# schematic.net
KiCad netlist of a schematic drawn in Altium Designer
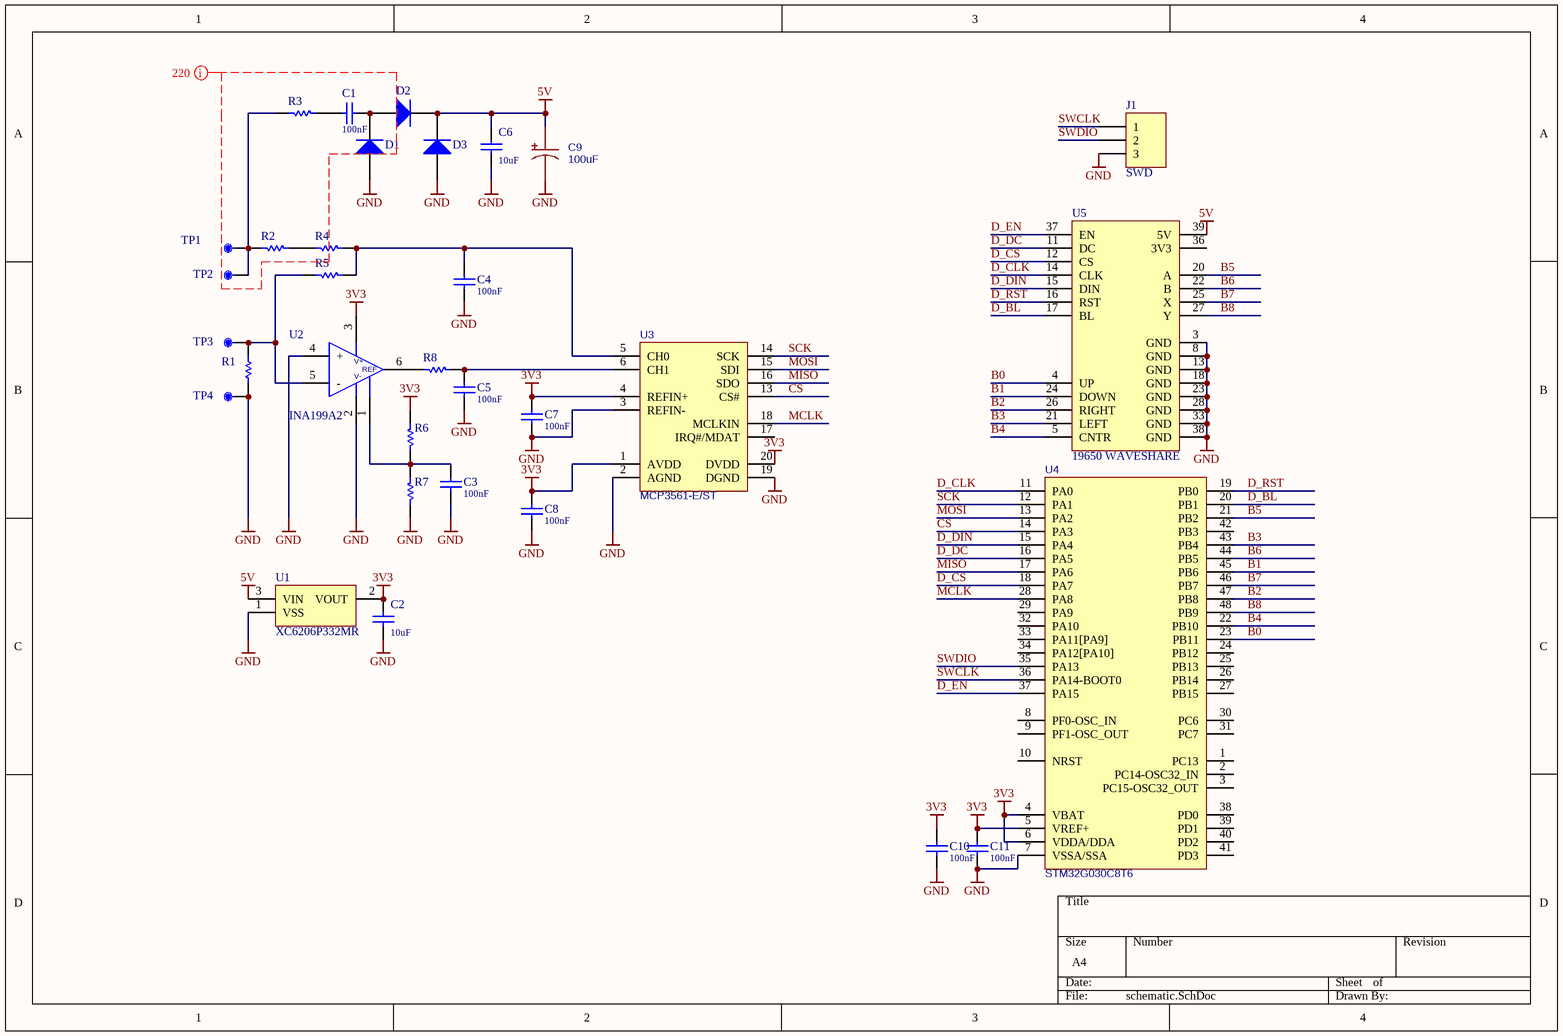
[diagram p0: schematic.SchDoc]

(export (version "E")
  (design (tool "Eeschema 10.0.6"))
  (components
    (comp (ref "C1")
      (value "100nF")
      (footprint "CAP-TH_27,5")
      (libsource (lib "Miscellaneous Devices") (part "CAP"))
    )
    (comp (ref "C2")
      (value "10uF")
      (footprint "C1206")
      (libsource (lib "Miscellaneous Devices") (part "CAP"))
    )
    (comp (ref "C3")
      (value "100nF")
      (footprint "C0402")
      (libsource (lib "Miscellaneous Devices") (part "CAP"))
    )
    (comp (ref "C4")
      (value "100nF")
      (footprint "C0402")
      (libsource (lib "Miscellaneous Devices") (part "CAP"))
    )
    (comp (ref "C5")
      (value "100nF")
      (footprint "C0402")
      (libsource (lib "Miscellaneous Devices") (part "CAP"))
    )
    (comp (ref "C6")
      (value "10uF")
      (footprint "C1206")
      (libsource (lib "Miscellaneous Devices") (part "CAP"))
    )
    (comp (ref "C7")
      (value "100nF")
      (footprint "C0402")
      (libsource (lib "Miscellaneous Devices") (part "CAP"))
    )
    (comp (ref "C8")
      (value "100nF")
      (footprint "C0402")
      (libsource (lib "Miscellaneous Devices") (part "CAP"))
    )
    (comp (ref "C9")
      (value "100uF")
      (footprint "C7343")
      (libsource (lib "altium-import") (part "root_0_220uF_"))
    )
    (comp (ref "C10")
      (value "100nF")
      (footprint "C0402")
      (libsource (lib "Miscellaneous Devices") (part "CAP"))
    )
    (comp (ref "C11")
      (value "100nF")
      (footprint "C0402")
      (libsource (lib "Miscellaneous Devices") (part "CAP"))
    )
    (comp (ref "D1")
      (value "~")
      (footprint "DO-41")
      (libsource (lib "Miscellaneous Devices") (part "US1M-13-F"))
    )
    (comp (ref "D2")
      (value "~")
      (footprint "DO-41")
      (libsource (lib "Miscellaneous Devices") (part "US1M-13-F"))
    )
    (comp (ref "D3")
      (value "~")
      (footprint "SMA")
      (libsource (lib "Miscellaneous Devices") (part "US1M-13-F"))
    )
    (comp (ref "J1")
      (value "SWD")
      (footprint "HDR-1X3")
      (libsource (lib "Miscellaneous Devices") (part "Header 3"))
    )
    (comp (ref "R1")
      (value "~")
      (footprint "R2512-WIDE")
      (libsource (lib "Miscellaneous Devices") (part "RES"))
    )
    (comp (ref "R2") (value "~") (footprint "R1206") (libsource (lib "Miscellaneous Devices") (part "RES")))
    (comp (ref "R3")
      (value "~")
      (footprint "RES-TH_20")
      (libsource (lib "Miscellaneous Devices") (part "RES"))
    )
    (comp (ref "R4") (value "~") (footprint "R1206") (libsource (lib "Miscellaneous Devices") (part "RES")))
    (comp (ref "R5") (value "~") (footprint "R1206") (libsource (lib "Miscellaneous Devices") (part "RES")))
    (comp (ref "R6") (value "~") (footprint "R0603") (libsource (lib "Miscellaneous Devices") (part "RES")))
    (comp (ref "R7") (value "~") (footprint "R0603") (libsource (lib "Miscellaneous Devices") (part "RES")))
    (comp (ref "R8") (value "~") (footprint "R0603") (libsource (lib "Miscellaneous Devices") (part "RES")))
    (comp (ref "TP1")
      (value "~")
      (footprint "TP2030_SMD")
      (libsource (lib "Miscellaneous Devices") (part "TP_Dup1"))
    )
    (comp (ref "TP2")
      (value "~")
      (footprint "TP2030_SMD")
      (libsource (lib "Miscellaneous Devices") (part "TP_Dup1"))
    )
    (comp (ref "TP3")
      (value "~")
      (footprint "TP2030_SMD")
      (libsource (lib "Miscellaneous Devices") (part "TP_Dup1"))
    )
    (comp (ref "TP4")
      (value "~")
      (footprint "TP2030_SMD")
      (libsource (lib "Miscellaneous Devices") (part "TP_Dup1"))
    )
    (comp (ref "U1")
      (value "XC6206P332MR")
      (footprint "SOT-23")
      (libsource (lib "Schlib1") (part "Component_4_1"))
    )
    (comp (ref "U2")
      (value "INA199A2")
      (footprint "SOT-363")
      (libsource (lib "Miscellaneous Devices") (part "MCP65R41T-2402"))
    )
    (comp (ref "U3")
      (value "MCP3561-E/ST")
      (footprint "SSOP-20")
      (libsource (lib "Schlib1") (part "MCP3561-E/ST"))
    )
    (comp (ref "U4")
      (value "STM32G030C8T6")
      (footprint "LQFP-48")
      (libsource (lib "Schlib1") (part "STM32G030C8T6"))
    )
    (comp (ref "U5")
      (value "19650 WAVESHARE")
      (footprint "DISP_19650_WS")
      (libsource (lib "Schlib1") (part "19650 WAVESHARE"))
    )
  )
  (nets
    (net (code "1") (name "/B0") (class "Default")
      (node (ref "U4") (pin "23") (pinfunction "PB11_23") (pintype "passive"))
      (node (ref "U5") (pin "4") (pinfunction "UP_4") (pintype "passive"))
    )
    (net (code "2") (name "/B1") (class "Default")
      (node (ref "U4") (pin "45") (pinfunction "PB6_45") (pintype "passive"))
      (node (ref "U5") (pin "24") (pinfunction "DOWN_24") (pintype "passive"))
    )
    (net (code "3") (name "/B2") (class "Default")
      (node (ref "U4") (pin "47") (pinfunction "PB8_47") (pintype "passive"))
      (node (ref "U5") (pin "26") (pinfunction "RIGHT_26") (pintype "passive"))
    )
    (net (code "4") (name "/B3") (class "Default")
      (node (ref "U4") (pin "43") (pinfunction "PB4_43") (pintype "passive"))
      (node (ref "U5") (pin "21") (pinfunction "LEFT_21") (pintype "passive"))
    )
    (net (code "5") (name "/B4") (class "Default")
      (node (ref "U4") (pin "22") (pinfunction "PB10_22") (pintype "passive"))
      (node (ref "U5") (pin "5") (pinfunction "CNTR_5") (pintype "passive"))
    )
    (net (code "6") (name "/B5") (class "Default")
      (node (ref "U4") (pin "21") (pinfunction "PB2_21") (pintype "passive"))
      (node (ref "U5") (pin "20") (pinfunction "A_20") (pintype "passive"))
    )
    (net (code "7") (name "/B6") (class "Default")
      (node (ref "U4") (pin "44") (pinfunction "PB5_44") (pintype "passive"))
      (node (ref "U5") (pin "22") (pinfunction "B_22") (pintype "passive"))
    )
    (net (code "8") (name "/B7") (class "Default")
      (node (ref "U4") (pin "46") (pinfunction "PB7_46") (pintype "passive"))
      (node (ref "U5") (pin "25") (pinfunction "X_25") (pintype "passive"))
    )
    (net (code "9") (name "/B8") (class "Default")
      (node (ref "U4") (pin "48") (pinfunction "PB9_48") (pintype "passive"))
      (node (ref "U5") (pin "27") (pinfunction "Y_27") (pintype "passive"))
    )
    (net (code "10") (name "/CS") (class "Default")
      (node (ref "U3") (pin "13") (pinfunction "CS#_13") (pintype "passive"))
      (node (ref "U4") (pin "14") (pinfunction "PA3_14") (pintype "passive"))
    )
    (net (code "11") (name "/D_BL") (class "Default")
      (node (ref "U4") (pin "20") (pinfunction "PB1_20") (pintype "passive"))
      (node (ref "U5") (pin "17") (pinfunction "BL_17") (pintype "passive"))
    )
    (net (code "12") (name "/D_CLK") (class "Default")
      (node (ref "U4") (pin "11") (pinfunction "PA0_11") (pintype "passive"))
      (node (ref "U5") (pin "14") (pinfunction "CLK_14") (pintype "passive"))
    )
    (net (code "13") (name "/D_CS") (class "Default")
      (node (ref "U4") (pin "18") (pinfunction "PA7_18") (pintype "passive"))
      (node (ref "U5") (pin "12") (pinfunction "CS_12") (pintype "passive"))
    )
    (net (code "14") (name "/D_DC") (class "Default")
      (node (ref "U4") (pin "16") (pinfunction "PA5_16") (pintype "passive"))
      (node (ref "U5") (pin "11") (pinfunction "DC_11") (pintype "passive"))
    )
    (net (code "15") (name "/D_DIN") (class "Default")
      (node (ref "U4") (pin "15") (pinfunction "PA4_15") (pintype "passive"))
      (node (ref "U5") (pin "15") (pinfunction "DIN_15") (pintype "passive"))
    )
    (net (code "16") (name "/D_EN") (class "Default")
      (node (ref "U4") (pin "37") (pinfunction "PA15_37") (pintype "passive"))
      (node (ref "U5") (pin "37") (pinfunction "EN_37") (pintype "passive"))
    )
    (net (code "17") (name "/D_RST") (class "Default")
      (node (ref "U4") (pin "19") (pinfunction "PB0_19") (pintype "passive"))
      (node (ref "U5") (pin "16") (pinfunction "RST_16") (pintype "passive"))
    )
    (net (code "18") (name "/MCLK") (class "Default")
      (node (ref "U3") (pin "18") (pinfunction "MCLKIN_18") (pintype "passive"))
      (node (ref "U4") (pin "28") (pinfunction "PA8_28") (pintype "passive"))
    )
    (net (code "19") (name "/MISO") (class "Default")
      (node (ref "U3") (pin "16") (pinfunction "SDO_16") (pintype "passive"))
      (node (ref "U4") (pin "17") (pinfunction "PA6_17") (pintype "passive"))
    )
    (net (code "20") (name "/MOSI") (class "Default")
      (node (ref "U3") (pin "15") (pinfunction "SDI_15") (pintype "passive"))
      (node (ref "U4") (pin "13") (pinfunction "PA2_13") (pintype "passive"))
    )
    (net (code "21") (name "/SCK") (class "Default")
      (node (ref "U3") (pin "14") (pinfunction "SCK_14") (pintype "passive"))
      (node (ref "U4") (pin "12") (pinfunction "PA1_12") (pintype "passive"))
    )
    (net (code "22") (name "/SWCLK") (class "Default")
      (node (ref "J1") (pin "1") (pinfunction "1_1") (pintype "passive"))
      (node (ref "U4") (pin "36") (pinfunction "PA14-BOOT0_36") (pintype "passive"))
    )
    (net (code "23") (name "/SWDIO") (class "Default")
      (node (ref "J1") (pin "2") (pinfunction "2_2") (pintype "passive"))
      (node (ref "U4") (pin "35") (pinfunction "PA13_35") (pintype "passive"))
    )
    (net (code "24") (name "3V3") (class "Default")
      (node (ref "C10") (pin "2") (pinfunction "2_2") (pintype "passive"))
      (node (ref "C11") (pin "2") (pinfunction "2_2") (pintype "passive"))
      (node (ref "C2") (pin "2") (pinfunction "2_2") (pintype "passive"))
      (node (ref "C7") (pin "2") (pinfunction "2_2") (pintype "passive"))
      (node (ref "C8") (pin "2") (pinfunction "2_2") (pintype "passive"))
      (node (ref "R6") (pin "2") (pinfunction "2_2") (pintype "passive"))
      (node (ref "U1") (pin "2") (pinfunction "VOUT_2") (pintype "passive"))
      (node (ref "U2") (pin "3") (pinfunction "V+_3") (pintype "passive"))
      (node (ref "U3") (pin "1") (pinfunction "AVDD_1") (pintype "passive"))
      (node (ref "U3") (pin "20") (pinfunction "DVDD_20") (pintype "passive"))
      (node (ref "U3") (pin "4") (pinfunction "REFIN+_4") (pintype "passive"))
      (node (ref "U4") (pin "4") (pinfunction "VBAT_4") (pintype "passive"))
      (node (ref "U4") (pin "5") (pinfunction "VREF+_5") (pintype "passive"))
      (node (ref "U4") (pin "6") (pinfunction "VDDA/DDA_6") (pintype "passive"))
    )
    (net (code "25") (name "5V") (class "Default")
      (node (ref "C6") (pin "2") (pinfunction "2_2") (pintype "passive"))
      (node (ref "C9") (pin "1") (pinfunction "1_1") (pintype "passive"))
      (node (ref "D2") (pin "2") (pinfunction "K_2") (pintype "passive"))
      (node (ref "D3") (pin "2") (pinfunction "K_2") (pintype "passive"))
      (node (ref "U1") (pin "3") (pinfunction "VIN_3") (pintype "passive"))
      (node (ref "U5") (pin "39") (pinfunction "5V_39") (pintype "passive"))
    )
    (net (code "26") (name "GND") (class "Default")
      (node (ref "C10") (pin "1") (pinfunction "1_1") (pintype "passive"))
      (node (ref "C11") (pin "1") (pinfunction "1_1") (pintype "passive"))
      (node (ref "C2") (pin "1") (pinfunction "1_1") (pintype "passive"))
      (node (ref "C3") (pin "1") (pinfunction "1_1") (pintype "passive"))
      (node (ref "C4") (pin "1") (pinfunction "1_1") (pintype "passive"))
      (node (ref "C5") (pin "1") (pinfunction "1_1") (pintype "passive"))
      (node (ref "C6") (pin "1") (pinfunction "1_1") (pintype "passive"))
      (node (ref "C7") (pin "1") (pinfunction "1_1") (pintype "passive"))
      (node (ref "C8") (pin "1") (pinfunction "1_1") (pintype "passive"))
      (node (ref "C9") (pin "2") (pinfunction "2_2") (pintype "passive"))
      (node (ref "D1") (pin "1") (pinfunction "A_1") (pintype "passive"))
      (node (ref "D3") (pin "1") (pinfunction "A_1") (pintype "passive"))
      (node (ref "J1") (pin "3") (pinfunction "3_3") (pintype "passive"))
      (node (ref "R1") (pin "2") (pinfunction "2_2") (pintype "passive"))
      (node (ref "R7") (pin "1") (pinfunction "1_1") (pintype "passive"))
      (node (ref "TP4") (pin "1") (pinfunction "1_1") (pintype "passive"))
      (node (ref "U1") (pin "1") (pinfunction "VSS_1") (pintype "passive"))
      (node (ref "U2") (pin "2") (pinfunction "GND_2") (pintype "power_in"))
      (node (ref "U2") (pin "4") (pinfunction "+_4") (pintype "passive"))
      (node (ref "U3") (pin "19") (pinfunction "DGND_19") (pintype "passive"))
      (node (ref "U3") (pin "2") (pinfunction "AGND_2") (pintype "passive"))
      (node (ref "U3") (pin "3") (pinfunction "REFIN-_3") (pintype "passive"))
      (node (ref "U4") (pin "7") (pinfunction "VSSA/SSA_7") (pintype "passive"))
      (node (ref "U5") (pin "13") (pinfunction "GND_13") (pintype "passive"))
      (node (ref "U5") (pin "18") (pinfunction "GND_18") (pintype "passive"))
      (node (ref "U5") (pin "23") (pinfunction "GND_23") (pintype "passive"))
      (node (ref "U5") (pin "28") (pinfunction "GND_28") (pintype "passive"))
      (node (ref "U5") (pin "3") (pinfunction "GND_3") (pintype "passive"))
      (node (ref "U5") (pin "33") (pinfunction "GND_33") (pintype "passive"))
      (node (ref "U5") (pin "38") (pinfunction "GND_38") (pintype "passive"))
      (node (ref "U5") (pin "8") (pinfunction "GND_8") (pintype "passive"))
    )
    (net (code "27") (name "Net-(C1-Pad2)") (class "Default")
      (node (ref "C1") (pin "2") (pinfunction "2_2") (pintype "passive"))
      (node (ref "R3") (pin "1") (pinfunction "1_1") (pintype "passive"))
    )
    (net (code "28") (name "Net-(D1-K)") (class "Default")
      (node (ref "C1") (pin "1") (pinfunction "1_1") (pintype "passive"))
      (node (ref "D1") (pin "2") (pinfunction "K_2") (pintype "passive"))
      (node (ref "D2") (pin "1") (pinfunction "A_1") (pintype "passive"))
    )
    (net (code "29") (name "Net-(R2-Pad1)") (class "Default")
      (node (ref "R2") (pin "1") (pinfunction "1_1") (pintype "passive"))
      (node (ref "R4") (pin "2") (pinfunction "2_2") (pintype "passive"))
    )
    (net (code "30") (name "Net-(R2-Pad2)") (class "Default")
      (node (ref "R2") (pin "2") (pinfunction "2_2") (pintype "passive"))
      (node (ref "R3") (pin "2") (pinfunction "2_2") (pintype "passive"))
      (node (ref "TP1") (pin "1") (pinfunction "1_1") (pintype "passive"))
      (node (ref "TP2") (pin "1") (pinfunction "1_1") (pintype "passive"))
    )
    (net (code "31") (name "Net-(U2--)") (class "Default")
      (node (ref "R1") (pin "1") (pinfunction "1_1") (pintype "passive"))
      (node (ref "R5") (pin "1") (pinfunction "1_1") (pintype "passive"))
      (node (ref "TP3") (pin "1") (pinfunction "1_1") (pintype "passive"))
      (node (ref "U2") (pin "5") (pinfunction "-_5") (pintype "passive"))
    )
    (net (code "32") (name "Net-(U2-OUT)") (class "Default")
      (node (ref "R8") (pin "2") (pinfunction "2_2") (pintype "passive"))
      (node (ref "U2") (pin "6") (pinfunction "OUT_6") (pintype "passive"))
    )
    (net (code "33") (name "Net-(U2-REF)") (class "Default")
      (node (ref "C3") (pin "2") (pinfunction "2_2") (pintype "passive"))
      (node (ref "R6") (pin "1") (pinfunction "1_1") (pintype "passive"))
      (node (ref "R7") (pin "2") (pinfunction "2_2") (pintype "passive"))
      (node (ref "U2") (pin "1") (pinfunction "REF_1") (pintype "power_in"))
    )
    (net (code "34") (name "Net-(U3-CH0)") (class "Default")
      (node (ref "C4") (pin "2") (pinfunction "2_2") (pintype "passive"))
      (node (ref "R4") (pin "1") (pinfunction "1_1") (pintype "passive"))
      (node (ref "R5") (pin "2") (pinfunction "2_2") (pintype "passive"))
      (node (ref "U3") (pin "5") (pinfunction "CH0_5") (pintype "passive"))
    )
    (net (code "35") (name "Net-(U3-CH1)") (class "Default")
      (node (ref "C5") (pin "2") (pinfunction "2_2") (pintype "passive"))
      (node (ref "R8") (pin "1") (pinfunction "1_1") (pintype "passive"))
      (node (ref "U3") (pin "6") (pinfunction "CH1_6") (pintype "passive"))
    )
    (net (code "36") (name "unconnected-(U3-IRQ#{slash}MDAT-Pad17)") (class "Default")
      (node (ref "U3") (pin "17") (pinfunction "IRQ#/MDAT_17") (pintype "passive"))
    )
    (net (code "37") (name "unconnected-(U4-NRST-Pad10)") (class "Default")
      (node (ref "U4") (pin "10") (pinfunction "NRST_10") (pintype "passive"))
    )
    (net (code "38") (name "unconnected-(U4-PA9-Pad29)") (class "Default")
      (node (ref "U4") (pin "29") (pinfunction "PA9_29") (pintype "passive"))
    )
    (net (code "39") (name "unconnected-(U4-PA10-Pad32)") (class "Default")
      (node (ref "U4") (pin "32") (pinfunction "PA10_32") (pintype "passive"))
    )
    (net (code "40") (name "unconnected-(U4-PA11[PA9]-Pad33)") (class "Default")
      (node (ref "U4") (pin "33") (pinfunction "PA11[PA9]_33") (pintype "passive"))
    )
    (net (code "41") (name "unconnected-(U4-PA12[PA10]-Pad34)") (class "Default")
      (node (ref "U4") (pin "34") (pinfunction "PA12[PA10]_34") (pintype "passive"))
    )
    (net (code "42") (name "unconnected-(U4-PB3-Pad42)") (class "Default")
      (node (ref "U4") (pin "42") (pinfunction "PB3_42") (pintype "passive"))
    )
    (net (code "43") (name "unconnected-(U4-PB12-Pad24)") (class "Default")
      (node (ref "U4") (pin "24") (pinfunction "PB12_24") (pintype "passive"))
    )
    (net (code "44") (name "unconnected-(U4-PB13-Pad25)") (class "Default")
      (node (ref "U4") (pin "25") (pinfunction "PB13_25") (pintype "passive"))
    )
    (net (code "45") (name "unconnected-(U4-PB14-Pad26)") (class "Default")
      (node (ref "U4") (pin "26") (pinfunction "PB14_26") (pintype "passive"))
    )
    (net (code "46") (name "unconnected-(U4-PB15-Pad27)") (class "Default")
      (node (ref "U4") (pin "27") (pinfunction "PB15_27") (pintype "passive"))
    )
    (net (code "47") (name "unconnected-(U4-PC6-Pad30)") (class "Default")
      (node (ref "U4") (pin "30") (pinfunction "PC6_30") (pintype "passive"))
    )
    (net (code "48") (name "unconnected-(U4-PC7-Pad31)") (class "Default")
      (node (ref "U4") (pin "31") (pinfunction "PC7_31") (pintype "passive"))
    )
    (net (code "49") (name "unconnected-(U4-PC13-Pad1)") (class "Default")
      (node (ref "U4") (pin "1") (pinfunction "PC13_1") (pintype "passive"))
    )
    (net (code "50") (name "unconnected-(U4-PC14-OSC32_IN-Pad2)") (class "Default")
      (node (ref "U4") (pin "2") (pinfunction "PC14-OSC32_IN_2") (pintype "passive"))
    )
    (net (code "51") (name "unconnected-(U4-PC15-OSC32_OUT-Pad3)") (class "Default")
      (node (ref "U4") (pin "3") (pinfunction "PC15-OSC32_OUT_3") (pintype "passive"))
    )
    (net (code "52") (name "unconnected-(U4-PD0-Pad38)") (class "Default")
      (node (ref "U4") (pin "38") (pinfunction "PD0_38") (pintype "passive"))
    )
    (net (code "53") (name "unconnected-(U4-PD1-Pad39)") (class "Default")
      (node (ref "U4") (pin "39") (pinfunction "PD1_39") (pintype "passive"))
    )
    (net (code "54") (name "unconnected-(U4-PD2-Pad40)") (class "Default")
      (node (ref "U4") (pin "40") (pinfunction "PD2_40") (pintype "passive"))
    )
    (net (code "55") (name "unconnected-(U4-PD3-Pad41)") (class "Default")
      (node (ref "U4") (pin "41") (pinfunction "PD3_41") (pintype "passive"))
    )
    (net (code "56") (name "unconnected-(U4-PF0-OSC_IN-Pad8)") (class "Default")
      (node (ref "U4") (pin "8") (pinfunction "PF0-OSC_IN_8") (pintype "passive"))
    )
    (net (code "57") (name "unconnected-(U4-PF1-OSC_OUT-Pad9)") (class "Default")
      (node (ref "U4") (pin "9") (pinfunction "PF1-OSC_OUT_9") (pintype "passive"))
    )
    (net (code "58") (name "unconnected-(U5-3V3-Pad36)") (class "Default")
      (node (ref "U5") (pin "36") (pinfunction "3V3_36") (pintype "passive"))
    )
  )
)
